# Schematic.net
KiCad netlist of a schematic drawn in Altium Designer
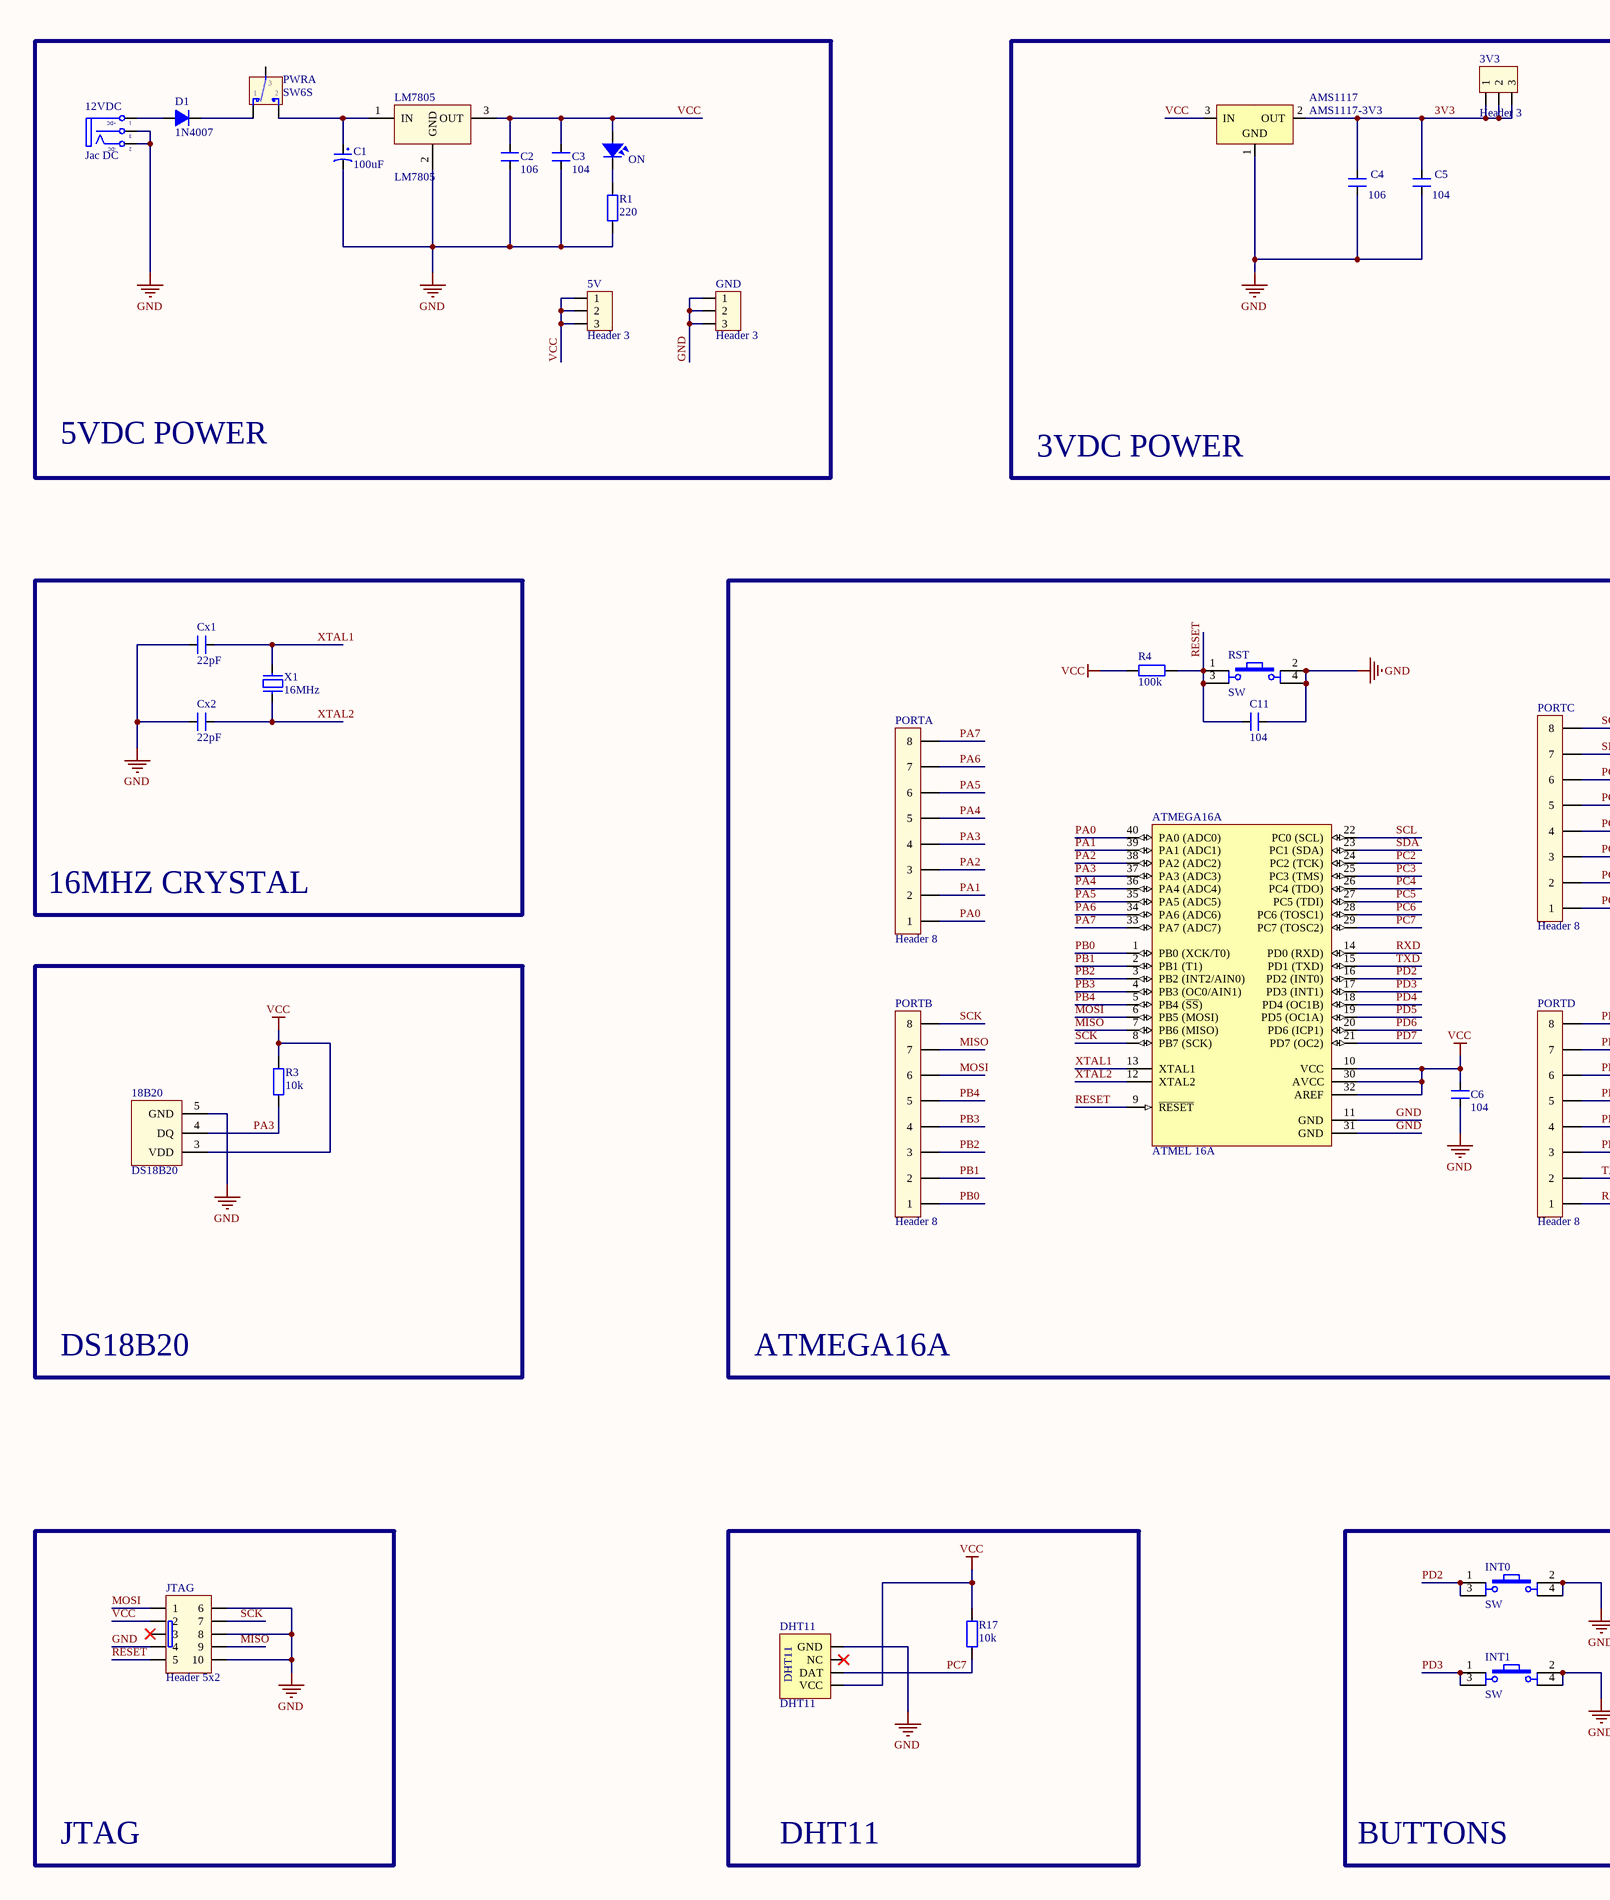
[diagram p0: Schematic.SchDoc, left]
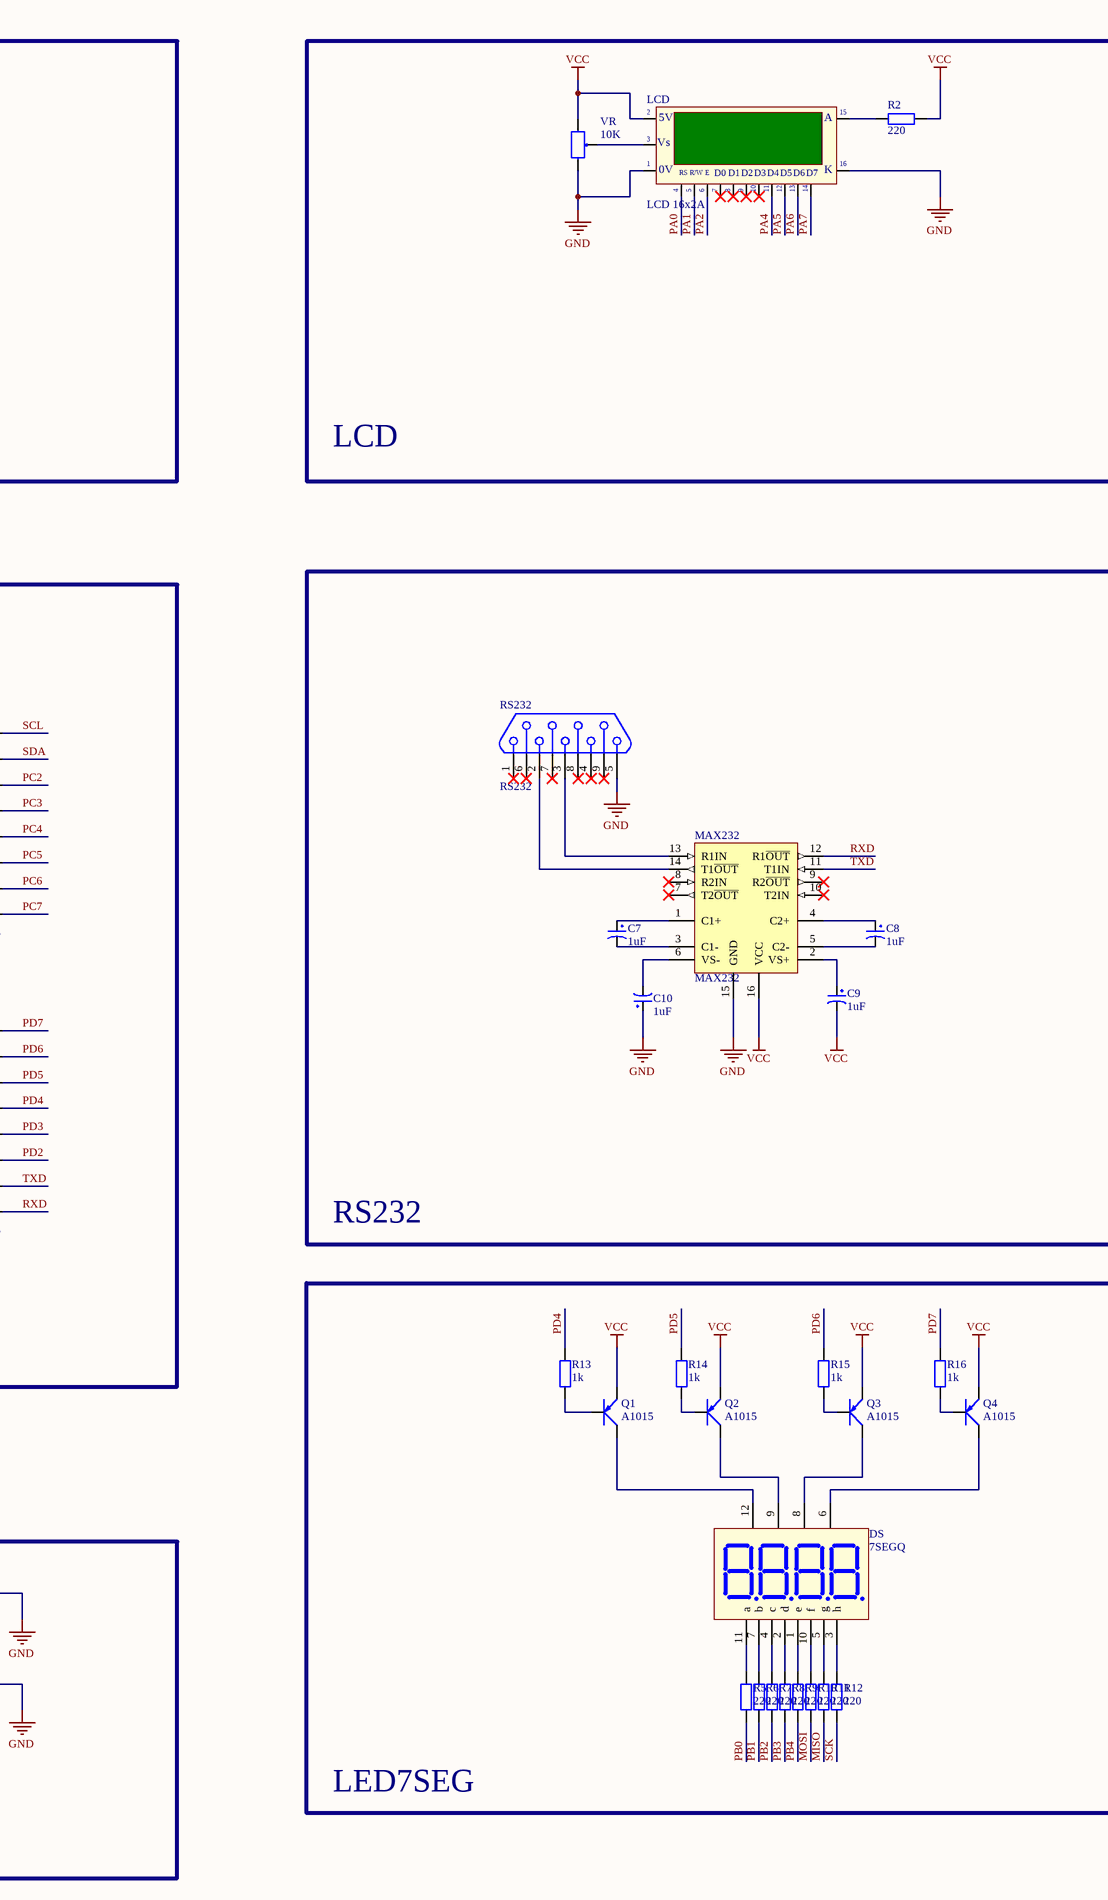
[diagram p1: Schematic.SchDoc, right]

(export (version "E")
  (design (tool "Eeschema 10.0.6"))
  (components
    (comp (ref "3V3")
      (value "Header 3")
      (footprint "HDR1X3")
      (description "Header 3 (Green)")
      (libsource (lib "syhaunguyen") (part "Hed3"))
    )
    (comp (ref "5V")
      (value "Header 3")
      (footprint "HDR1X3")
      (description "Header 3 (Green)")
      (libsource (lib "echipkool-com-library") (part "Hed3"))
    )
    (comp (ref "12VDC")
      (value "Jac DC")
      (footprint "DC-IN")
      (description "Jac DC input")
      (libsource (lib "My Library") (part "DCIN"))
    )
    (comp (ref "18B20")
      (value "DS18B20")
      (footprint "DS18S20")
      (description "High Precision  1-Wire® Digital Thermometer")
      (libsource (lib "syhaunguyen") (part "DS18S20"))
    )
    (comp (ref "AMS1117")
      (value "AMS1117-3V3")
      (footprint "AMS1117-3.3V")
      (description "Linear Voltage Regulator 3.3V 1A 15V Max SOT-223")
      (libsource (lib "lpson") (part "AMS1117-3V3"))
    )
    (comp (ref "ATMEGA16A")
      (value "ATMEL 16A")
      (footprint "DIP40/W0.6")
      (description "8-Bit AVR Microcontroller with 16K Bytes of In-System Programmable Flash Memory")
      (libsource (lib "My Library") (part "ATmega16A-PU"))
    )
    (comp (ref "C1")
      (value "100uF")
      (footprint "CP1/2")
      (description "Cap P  0,1uF < 22uF , 16 - 50V")
      (libsource (lib "echipkool-com-library") (part "CP1"))
    )
    (comp (ref "C2")
      (value "106")
      (footprint "CN2")
      (description "Cap np 104 => 105pF")
      (libsource (lib "echipkool-com-library") (part "CN2"))
    )
    (comp (ref "C3")
      (value "104")
      (footprint "CN2")
      (description "Cap np 104 => 105pF")
      (libsource (lib "echipkool-com-library") (part "CN2"))
    )
    (comp (ref "C4")
      (value "106")
      (footprint "CN2")
      (description "Cap np 104 => 105pF")
      (libsource (lib "syhaunguyen") (part "CN2"))
    )
    (comp (ref "C5")
      (value "104")
      (footprint "CN2")
      (description "Cap np 104 => 105pF")
      (libsource (lib "syhaunguyen") (part "CN2"))
    )
    (comp (ref "C6")
      (value "104")
      (footprint "CN2")
      (fields (field (name "DESIGNED BY") "VanDungEvn"))
      (libsource (lib "syhaunguyen") (part "CN"))
    )
    (comp (ref "C7")
      (value "1uF")
      (footprint "CP1/2")
      (description "Cap P  0,1uF < 22uF , 16 - 50V")
      (libsource (lib "My Library") (part "CP1"))
    )
    (comp (ref "C8")
      (value "1uF")
      (footprint "CP1/2")
      (description "Cap P  0,1uF < 22uF , 16 - 50V")
      (libsource (lib "My Library") (part "CP1"))
    )
    (comp (ref "C9")
      (value "1uF")
      (footprint "CP1/2")
      (description "Cap P  0,1uF < 22uF , 16 - 50V")
      (libsource (lib "My Library") (part "CP1"))
    )
    (comp (ref "C10")
      (value "1uF")
      (footprint "CP1/2")
      (description "Cap P  0,1uF < 22uF , 16 - 50V")
      (libsource (lib "My Library") (part "CP1"))
    )
    (comp (ref "C11")
      (value "104")
      (footprint "CN2")
      (description "Cap np 104 => 105pF")
      (libsource (lib "syhaunguyen") (part "CN2"))
    )
    (comp (ref "Cx1")
      (value "22pF")
      (footprint "CN1")
      (description "Cremic For Xtal 1pF => 100pF")
      (libsource (lib "syhaunguyen") (part "CN0"))
    )
    (comp (ref "Cx2")
      (value "22pF")
      (footprint "CN1")
      (description "Cremic For Xtal 1pF => 100pF")
      (libsource (lib "syhaunguyen") (part "CN0"))
    )
    (comp (ref "D1")
      (value "1N4007")
      (footprint "D1A")
      (description "Diode 1A")
      (libsource (lib "echipkool-com-library") (part "D1A"))
    )
    (comp (ref "DHT11")
      (value "DHT11")
      (footprint "JP4-C1T")
      (fields
        (field (name "MANUFACTURER") "Würth Elektronik eiSos GmbH")
        (field (name "PARTNO") "613004143121")
        (field (name "CREATED BY") "Karrer Zheng")
      )
      (libsource (lib "My Library") (part "DHT11"))
    )
    (comp (ref "DS")
      (value "7SEGQ")
      (footprint "LED7SEG-4-0.56")
      (description "Four 7 Seg Dipslay")
      (libsource (lib "My Library") (part "LED7SEG-4"))
    )
    (comp (ref "GND")
      (value "Header 3")
      (footprint "HDR1X3")
      (description "Header 3 (Green)")
      (libsource (lib "echipkool-com-library") (part "Hed3"))
    )
    (comp (ref "INT0")
      (value "SW")
      (footprint "SW4")
      (description "Switch button 4 pin")
      (libsource (lib "syhaunguyen") (part "SW4"))
    )
    (comp (ref "INT1")
      (value "SW")
      (footprint "SW4")
      (description "Switch button 4 pin")
      (libsource (lib "syhaunguyen") (part "SW4"))
    )
    (comp (ref "JTAG")
      (value "Header 5x2")
      (footprint "Hed2X5")
      (libsource (lib "syhaunguyen") (part "HED5x2"))
    )
    (comp (ref "LCD")
      (value "LCD 16x2A")
      (footprint "LPON_DISPLAY:LCD16x2")
      (description "LCD dipslay 16 char, 2 line")
      (libsource (lib "lpson") (part "LCD16x2A"))
    )
    (comp (ref "LM7805")
      (value "LM7805")
      (footprint "QTO-220")
      (description "On ap +, from + 5 to + 24VDC")
      (libsource (lib "My Library") (part "LM78xx"))
    )
    (comp (ref "MAX232")
      (value "MAX232")
      (footprint "DIP16/W0.3")
      (description "Dual EIA-232 Driver/Receiver")
      (libsource (lib "echipkool-com-library") (part "MAX232"))
    )
    (comp (ref "ON")
      (value "LED")
      (footprint "LED-3")
      (description "LED Single colour Green and Red")
      (libsource (lib "echipkool-com-library") (part "LED"))
    )
    (comp (ref "PORTA")
      (value "Header 8")
      (footprint "HDR1X8")
      (description "Header 8 Vit Broad")
      (libsource (lib "syhaunguyen") (part "HED8V"))
    )
    (comp (ref "PORTB")
      (value "Header 8")
      (footprint "HDR1X8")
      (description "Header 8 Vit Broad")
      (libsource (lib "syhaunguyen") (part "HED8V"))
    )
    (comp (ref "PORTC")
      (value "Header 8")
      (footprint "HDR1X8")
      (description "Header 8 Vit Broad")
      (libsource (lib "syhaunguyen") (part "HED8V"))
    )
    (comp (ref "PORTD")
      (value "Header 8")
      (footprint "HDR1X8")
      (description "Header 8 Vit Broad")
      (libsource (lib "syhaunguyen") (part "HED8V"))
    )
    (comp (ref "PWR")
      (value "SW6S")
      (footprint "SW6")
      (description "SW-DTDP - 6 Pin")
      (libsource (lib "echipkool-com-library") (part "SW6S"))
    )
    (comp (ref "Q1")
      (value "A1015")
      (footprint "QTO-92")
      (description "PNP 600mW, ECB")
      (libsource (lib "syhaunguyen") (part "A1015"))
    )
    (comp (ref "Q2")
      (value "A1015")
      (footprint "QTO-92")
      (description "PNP 600mW, ECB")
      (libsource (lib "syhaunguyen") (part "A1015"))
    )
    (comp (ref "Q3")
      (value "A1015")
      (footprint "QTO-92")
      (description "PNP 600mW, ECB")
      (libsource (lib "syhaunguyen") (part "A1015"))
    )
    (comp (ref "Q4")
      (value "A1015")
      (footprint "QTO-92")
      (description "PNP 600mW, ECB")
      (libsource (lib "syhaunguyen") (part "A1015"))
    )
    (comp (ref "R1")
      (value "220")
      (footprint "R1/4W")
      (description "Resistor 1/4W")
      (libsource (lib "echipkool-com-library") (part "R1/4W"))
    )
    (comp (ref "R2")
      (value "220")
      (footprint "R1/4W")
      (description "Resistor 1/4W")
      (libsource (lib "lpson") (part "R1/4W"))
    )
    (comp (ref "R3")
      (value "10k")
      (footprint "R1/4W")
      (description "Resistor 1/4W")
      (libsource (lib "syhaunguyen") (part "R1/4W"))
    )
    (comp (ref "R4")
      (value "100k")
      (footprint "R1/4W")
      (description "Resistor 1/4W")
      (libsource (lib "syhaunguyen") (part "R1/4W"))
    )
    (comp (ref "R5")
      (value "220")
      (footprint "R1/4W")
      (description "Resistor 1/4W")
      (libsource (lib "syhaunguyen") (part "R1/4W"))
    )
    (comp (ref "R6")
      (value "220")
      (footprint "R1/4W")
      (description "Resistor 1/4W")
      (libsource (lib "syhaunguyen") (part "R1/4W"))
    )
    (comp (ref "R7")
      (value "220")
      (footprint "R1/4W")
      (description "Resistor 1/4W")
      (libsource (lib "syhaunguyen") (part "R1/4W"))
    )
    (comp (ref "R8")
      (value "220")
      (footprint "R1/4W")
      (description "Resistor 1/4W")
      (libsource (lib "syhaunguyen") (part "R1/4W"))
    )
    (comp (ref "R9")
      (value "220")
      (footprint "R1/4W")
      (description "Resistor 1/4W")
      (libsource (lib "syhaunguyen") (part "R1/4W"))
    )
    (comp (ref "R10")
      (value "220")
      (footprint "R1/4W")
      (description "Resistor 1/4W")
      (libsource (lib "syhaunguyen") (part "R1/4W"))
    )
    (comp (ref "R11")
      (value "220")
      (footprint "R1/4W")
      (description "Resistor 1/4W")
      (libsource (lib "syhaunguyen") (part "R1/4W"))
    )
    (comp (ref "R12")
      (value "220")
      (footprint "R1/4W")
      (description "Resistor 1/4W")
      (libsource (lib "syhaunguyen") (part "R1/4W"))
    )
    (comp (ref "R13")
      (value "1k")
      (footprint "R1/4W")
      (description "Resistor 1/4W")
      (libsource (lib "syhaunguyen") (part "R1/4W"))
    )
    (comp (ref "R14")
      (value "1k")
      (footprint "R1/4W")
      (description "Resistor 1/4W")
      (libsource (lib "syhaunguyen") (part "R1/4W"))
    )
    (comp (ref "R15")
      (value "1k")
      (footprint "R1/4W")
      (description "Resistor 1/4W")
      (libsource (lib "syhaunguyen") (part "R1/4W"))
    )
    (comp (ref "R16")
      (value "1k")
      (footprint "R1/4W")
      (description "Resistor 1/4W")
      (libsource (lib "syhaunguyen") (part "R1/4W"))
    )
    (comp (ref "R17")
      (value "10k")
      (footprint "R1/4W")
      (description "Resistor 1/4W")
      (libsource (lib "syhaunguyen") (part "R1/4W"))
    )
    (comp (ref "RS232") (value "RS232") (footprint "DSB 9-M") (libsource (lib "syhaunguyen") (part "COM")))
    (comp (ref "RST")
      (value "SW")
      (footprint "SW4")
      (description "Switch button 4 pin")
      (libsource (lib "syhaunguyen") (part "SW4"))
    )
    (comp (ref "VR")
      (value "10K")
      (footprint "VR1")
      (description "Var Resistor")
      (libsource (lib "syhaunguyen") (part "VR"))
    )
    (comp (ref "X1")
      (value "16MHz")
      (footprint "XT2")
      (description "Crystal For all Crystal 2pin.")
      (libsource (lib "syhaunguyen") (part "XT2"))
    )
  )
  (nets
    (net (code "1") (name "/3V3") (class "Default")
      (node (ref "3V3") (pin "1") (pinfunction "1_1") (pintype "passive"))
      (node (ref "3V3") (pin "2") (pinfunction "2_2") (pintype "passive"))
      (node (ref "3V3") (pin "3") (pinfunction "3_3") (pintype "passive"))
      (node (ref "AMS1117") (pin "2") (pinfunction "OUT_2") (pintype "power_in"))
      (node (ref "C4") (pin "2") (pinfunction "2_2") (pintype "passive"))
      (node (ref "C5") (pin "2") (pinfunction "2_2") (pintype "passive"))
    )
    (net (code "2") (name "/MISO") (class "Default")
      (node (ref "ATMEGA16A") (pin "7") (pinfunction "PB6_(MISO)_7") (pintype "bidirectional"))
      (node (ref "JTAG") (pin "9") (pinfunction "9_9") (pintype "passive"))
      (node (ref "PORTB") (pin "7") (pinfunction "7_7") (pintype "passive"))
      (node (ref "R11") (pin "1") (pinfunction "1_1") (pintype "passive"))
    )
    (net (code "3") (name "/MOSI") (class "Default")
      (node (ref "ATMEGA16A") (pin "6") (pinfunction "PB5_(MOSI)_6") (pintype "bidirectional"))
      (node (ref "JTAG") (pin "1") (pinfunction "1_1") (pintype "passive"))
      (node (ref "PORTB") (pin "6") (pinfunction "6_6") (pintype "passive"))
      (node (ref "R10") (pin "1") (pinfunction "1_1") (pintype "passive"))
    )
    (net (code "4") (name "/PA0") (class "Default")
      (node (ref "ATMEGA16A") (pin "40") (pinfunction "PA0_(ADC0)_40") (pintype "bidirectional"))
      (node (ref "LCD") (pin "4") (pinfunction "RS_4") (pintype "passive"))
      (node (ref "PORTA") (pin "1") (pinfunction "1_1") (pintype "passive"))
    )
    (net (code "5") (name "/PA1") (class "Default")
      (node (ref "ATMEGA16A") (pin "39") (pinfunction "PA1_(ADC1)_39") (pintype "bidirectional"))
      (node (ref "LCD") (pin "5") (pinfunction "R/~{W}_5") (pintype "passive"))
      (node (ref "PORTA") (pin "2") (pinfunction "2_2") (pintype "passive"))
    )
    (net (code "6") (name "/PA2") (class "Default")
      (node (ref "ATMEGA16A") (pin "38") (pinfunction "PA2_(ADC2)_38") (pintype "bidirectional"))
      (node (ref "LCD") (pin "6") (pinfunction "~{EN}_6") (pintype "passive"))
      (node (ref "PORTA") (pin "3") (pinfunction "3_3") (pintype "passive"))
    )
    (net (code "7") (name "/PA3") (class "Default")
      (node (ref "18B20") (pin "4") (pinfunction "DQ_4") (pintype "passive"))
      (node (ref "ATMEGA16A") (pin "37") (pinfunction "PA3_(ADC3)_37") (pintype "bidirectional"))
      (node (ref "PORTA") (pin "4") (pinfunction "4_4") (pintype "passive"))
      (node (ref "R3") (pin "1") (pinfunction "1_1") (pintype "passive"))
    )
    (net (code "8") (name "/PA4") (class "Default")
      (node (ref "ATMEGA16A") (pin "36") (pinfunction "PA4_(ADC4)_36") (pintype "bidirectional"))
      (node (ref "LCD") (pin "11") (pinfunction "D4_11") (pintype "passive"))
      (node (ref "PORTA") (pin "5") (pinfunction "5_5") (pintype "passive"))
    )
    (net (code "9") (name "/PA5") (class "Default")
      (node (ref "ATMEGA16A") (pin "35") (pinfunction "PA5_(ADC5)_35") (pintype "bidirectional"))
      (node (ref "LCD") (pin "12") (pinfunction "D5_12") (pintype "passive"))
      (node (ref "PORTA") (pin "6") (pinfunction "6_6") (pintype "passive"))
    )
    (net (code "10") (name "/PA6") (class "Default")
      (node (ref "ATMEGA16A") (pin "34") (pinfunction "PA6_(ADC6)_34") (pintype "bidirectional"))
      (node (ref "LCD") (pin "13") (pinfunction "D6_13") (pintype "passive"))
      (node (ref "PORTA") (pin "7") (pinfunction "7_7") (pintype "passive"))
    )
    (net (code "11") (name "/PA7") (class "Default")
      (node (ref "ATMEGA16A") (pin "33") (pinfunction "PA7_(ADC7)_33") (pintype "bidirectional"))
      (node (ref "LCD") (pin "14") (pinfunction "D7_14") (pintype "passive"))
      (node (ref "PORTA") (pin "8") (pinfunction "8_8") (pintype "passive"))
    )
    (net (code "12") (name "/PB0") (class "Default")
      (node (ref "ATMEGA16A") (pin "1") (pinfunction "PB0_(XCK/T0)_1") (pintype "bidirectional"))
      (node (ref "PORTB") (pin "1") (pinfunction "1_1") (pintype "passive"))
      (node (ref "R5") (pin "1") (pinfunction "1_1") (pintype "passive"))
    )
    (net (code "13") (name "/PB1") (class "Default")
      (node (ref "ATMEGA16A") (pin "2") (pinfunction "PB1_(T1)_2") (pintype "bidirectional"))
      (node (ref "PORTB") (pin "2") (pinfunction "2_2") (pintype "passive"))
      (node (ref "R6") (pin "1") (pinfunction "1_1") (pintype "passive"))
    )
    (net (code "14") (name "/PB2") (class "Default")
      (node (ref "ATMEGA16A") (pin "3") (pinfunction "PB2_(INT2/AIN0)_3") (pintype "bidirectional"))
      (node (ref "PORTB") (pin "3") (pinfunction "3_3") (pintype "passive"))
      (node (ref "R7") (pin "1") (pinfunction "1_1") (pintype "passive"))
    )
    (net (code "15") (name "/PB3") (class "Default")
      (node (ref "ATMEGA16A") (pin "4") (pinfunction "PB3_(OC0/AIN1)_4") (pintype "bidirectional"))
      (node (ref "PORTB") (pin "4") (pinfunction "4_4") (pintype "passive"))
      (node (ref "R8") (pin "1") (pinfunction "1_1") (pintype "passive"))
    )
    (net (code "16") (name "/PB4") (class "Default")
      (node (ref "ATMEGA16A") (pin "5") (pinfunction "PB4_(~{SS})_5") (pintype "bidirectional"))
      (node (ref "PORTB") (pin "5") (pinfunction "5_5") (pintype "passive"))
      (node (ref "R9") (pin "1") (pinfunction "1_1") (pintype "passive"))
    )
    (net (code "17") (name "/PC2") (class "Default")
      (node (ref "ATMEGA16A") (pin "24") (pinfunction "PC2_(TCK)_24") (pintype "bidirectional"))
      (node (ref "PORTC") (pin "6") (pinfunction "6_6") (pintype "passive"))
    )
    (net (code "18") (name "/PC3") (class "Default")
      (node (ref "ATMEGA16A") (pin "25") (pinfunction "PC3_(TMS)_25") (pintype "bidirectional"))
      (node (ref "PORTC") (pin "5") (pinfunction "5_5") (pintype "passive"))
    )
    (net (code "19") (name "/PC4") (class "Default")
      (node (ref "ATMEGA16A") (pin "26") (pinfunction "PC4_(TDO)_26") (pintype "bidirectional"))
      (node (ref "PORTC") (pin "4") (pinfunction "4_4") (pintype "passive"))
    )
    (net (code "20") (name "/PC5") (class "Default")
      (node (ref "ATMEGA16A") (pin "27") (pinfunction "PC5_(TDI)_27") (pintype "bidirectional"))
      (node (ref "PORTC") (pin "3") (pinfunction "3_3") (pintype "passive"))
    )
    (net (code "21") (name "/PC6") (class "Default")
      (node (ref "ATMEGA16A") (pin "28") (pinfunction "PC6_(TOSC1)_28") (pintype "bidirectional"))
      (node (ref "PORTC") (pin "2") (pinfunction "2_2") (pintype "passive"))
    )
    (net (code "22") (name "/PC7") (class "Default")
      (node (ref "ATMEGA16A") (pin "29") (pinfunction "PC7_(TOSC2)_29") (pintype "bidirectional"))
      (node (ref "DHT11") (pin "2") (pinfunction "DAT_2") (pintype "passive"))
      (node (ref "PORTC") (pin "1") (pinfunction "1_1") (pintype "passive"))
      (node (ref "R17") (pin "1") (pinfunction "1_1") (pintype "passive"))
    )
    (net (code "23") (name "/PD2") (class "Default")
      (node (ref "ATMEGA16A") (pin "16") (pinfunction "PD2_(INT0)_16") (pintype "bidirectional"))
      (node (ref "INT0") (pin "1") (pintype "passive"))
      (node (ref "INT0") (pin "3") (pintype "passive"))
      (node (ref "PORTD") (pin "3") (pinfunction "3_3") (pintype "passive"))
    )
    (net (code "24") (name "/PD3") (class "Default")
      (node (ref "ATMEGA16A") (pin "17") (pinfunction "PD3_(INT1)_17") (pintype "bidirectional"))
      (node (ref "INT1") (pin "1") (pintype "passive"))
      (node (ref "INT1") (pin "3") (pintype "passive"))
      (node (ref "PORTD") (pin "4") (pinfunction "4_4") (pintype "passive"))
    )
    (net (code "25") (name "/PD4") (class "Default")
      (node (ref "ATMEGA16A") (pin "18") (pinfunction "PD4_(OC1B)_18") (pintype "bidirectional"))
      (node (ref "PORTD") (pin "5") (pinfunction "5_5") (pintype "passive"))
      (node (ref "R13") (pin "2") (pinfunction "2_2") (pintype "passive"))
    )
    (net (code "26") (name "/PD5") (class "Default")
      (node (ref "ATMEGA16A") (pin "19") (pinfunction "PD5_(OC1A)_19") (pintype "bidirectional"))
      (node (ref "PORTD") (pin "6") (pinfunction "6_6") (pintype "passive"))
      (node (ref "R14") (pin "2") (pinfunction "2_2") (pintype "passive"))
    )
    (net (code "27") (name "/PD6") (class "Default")
      (node (ref "ATMEGA16A") (pin "20") (pinfunction "PD6_(ICP1)_20") (pintype "bidirectional"))
      (node (ref "PORTD") (pin "7") (pinfunction "7_7") (pintype "passive"))
      (node (ref "R15") (pin "2") (pinfunction "2_2") (pintype "passive"))
    )
    (net (code "28") (name "/PD7") (class "Default")
      (node (ref "ATMEGA16A") (pin "21") (pinfunction "PD7_(OC2)_21") (pintype "bidirectional"))
      (node (ref "PORTD") (pin "8") (pinfunction "8_8") (pintype "passive"))
      (node (ref "R16") (pin "2") (pinfunction "2_2") (pintype "passive"))
    )
    (net (code "29") (name "/RESET") (class "Default")
      (node (ref "ATMEGA16A") (pin "9") (pinfunction "~{RESET}_9") (pintype "input"))
      (node (ref "C11") (pin "1") (pinfunction "1_1") (pintype "passive"))
      (node (ref "JTAG") (pin "5") (pinfunction "5_5") (pintype "passive"))
      (node (ref "R4") (pin "2") (pinfunction "2_2") (pintype "passive"))
      (node (ref "RST") (pin "1") (pintype "passive"))
      (node (ref "RST") (pin "3") (pintype "passive"))
    )
    (net (code "30") (name "/RXD") (class "Default")
      (node (ref "ATMEGA16A") (pin "14") (pinfunction "PD0_(RXD)_14") (pintype "bidirectional"))
      (node (ref "MAX232") (pin "12") (pinfunction "R1~{OUT}_12") (pintype "output"))
      (node (ref "PORTD") (pin "1") (pinfunction "1_1") (pintype "passive"))
    )
    (net (code "31") (name "/SCK") (class "Default")
      (node (ref "ATMEGA16A") (pin "8") (pinfunction "PB7_(SCK)_8") (pintype "bidirectional"))
      (node (ref "JTAG") (pin "7") (pinfunction "7_7") (pintype "passive"))
      (node (ref "PORTB") (pin "8") (pinfunction "8_8") (pintype "passive"))
      (node (ref "R12") (pin "1") (pinfunction "1_1") (pintype "passive"))
    )
    (net (code "32") (name "/SCL") (class "Default")
      (node (ref "ATMEGA16A") (pin "22") (pinfunction "PC0_(SCL)_22") (pintype "bidirectional"))
      (node (ref "PORTC") (pin "8") (pinfunction "8_8") (pintype "passive"))
    )
    (net (code "33") (name "/SDA") (class "Default")
      (node (ref "ATMEGA16A") (pin "23") (pinfunction "PC1_(SDA)_23") (pintype "bidirectional"))
      (node (ref "PORTC") (pin "7") (pinfunction "7_7") (pintype "passive"))
    )
    (net (code "34") (name "/TXD") (class "Default")
      (node (ref "ATMEGA16A") (pin "15") (pinfunction "PD1_(TXD)_15") (pintype "bidirectional"))
      (node (ref "MAX232") (pin "11") (pinfunction "T1IN_11") (pintype "input"))
      (node (ref "PORTD") (pin "2") (pinfunction "2_2") (pintype "passive"))
    )
    (net (code "35") (name "/XTAL1") (class "Default")
      (node (ref "ATMEGA16A") (pin "13") (pinfunction "XTAL1_13") (pintype "passive"))
      (node (ref "Cx1") (pin "2") (pinfunction "2_2") (pintype "passive"))
      (node (ref "X1") (pin "2") (pinfunction "2_2") (pintype "passive"))
    )
    (net (code "36") (name "/XTAL2") (class "Default")
      (node (ref "ATMEGA16A") (pin "12") (pinfunction "XTAL2_12") (pintype "passive"))
      (node (ref "Cx2") (pin "2") (pinfunction "2_2") (pintype "passive"))
      (node (ref "X1") (pin "1") (pinfunction "1_1") (pintype "passive"))
    )
    (net (code "37") (name "GND") (class "Default")
      (node (ref "12VDC") (pin "2") (pinfunction "TN_2") (pintype "passive"))
      (node (ref "12VDC") (pin "3") (pinfunction "S_3") (pintype "power_in"))
      (node (ref "18B20") (pin "5") (pinfunction "GND_5") (pintype "passive"))
      (node (ref "AMS1117") (pin "1") (pinfunction "GND_1") (pintype "power_in"))
      (node (ref "ATMEGA16A") (pin "11") (pinfunction "GND_11") (pintype "power_in"))
      (node (ref "ATMEGA16A") (pin "31") (pinfunction "GND_31") (pintype "power_in"))
      (node (ref "C1") (pin "2") (pinfunction "2_2") (pintype "passive"))
      (node (ref "C10") (pin "1") (pinfunction "1_1") (pintype "passive"))
      (node (ref "C11") (pin "2") (pinfunction "2_2") (pintype "passive"))
      (node (ref "C2") (pin "1") (pinfunction "1_1") (pintype "passive"))
      (node (ref "C3") (pin "1") (pinfunction "1_1") (pintype "passive"))
      (node (ref "C4") (pin "1") (pinfunction "1_1") (pintype "passive"))
      (node (ref "C5") (pin "1") (pinfunction "1_1") (pintype "passive"))
      (node (ref "C6") (pin "1") (pinfunction "1_1") (pintype "passive"))
      (node (ref "Cx1") (pin "1") (pinfunction "1_1") (pintype "passive"))
      (node (ref "Cx2") (pin "1") (pinfunction "1_1") (pintype "passive"))
      (node (ref "DHT11") (pin "4") (pinfunction "GND_4") (pintype "passive"))
      (node (ref "GND") (pin "1") (pinfunction "1_1") (pintype "passive"))
      (node (ref "GND") (pin "2") (pinfunction "2_2") (pintype "passive"))
      (node (ref "GND") (pin "3") (pinfunction "3_3") (pintype "passive"))
      (node (ref "INT0") (pin "2") (pintype "passive"))
      (node (ref "INT0") (pin "4") (pintype "passive"))
      (node (ref "INT1") (pin "2") (pintype "passive"))
      (node (ref "INT1") (pin "4") (pintype "passive"))
      (node (ref "JTAG") (pin "10") (pinfunction "10_10") (pintype "passive"))
      (node (ref "JTAG") (pin "4") (pinfunction "4_4") (pintype "passive"))
      (node (ref "JTAG") (pin "6") (pinfunction "6_6") (pintype "passive"))
      (node (ref "JTAG") (pin "8") (pinfunction "8_8") (pintype "passive"))
      (node (ref "LCD") (pin "1") (pinfunction "GND_1") (pintype "passive"))
      (node (ref "LCD") (pin "16") (pinfunction "K_16") (pintype "passive"))
      (node (ref "LM7805") (pin "2") (pinfunction "GND_2") (pintype "passive"))
      (node (ref "MAX232") (pin "15") (pinfunction "GND_15") (pintype "power_in"))
      (node (ref "R1") (pin "1") (pinfunction "1_1") (pintype "passive"))
      (node (ref "RS232") (pin "5") (pinfunction "5_5") (pintype "passive"))
      (node (ref "RST") (pin "2") (pintype "passive"))
      (node (ref "RST") (pin "4") (pintype "passive"))
      (node (ref "VR") (pin "3") (pinfunction "3_3") (pintype "passive"))
    )
    (net (code "38") (name "Net-(12VDC-T)") (class "Default")
      (node (ref "12VDC") (pin "1") (pinfunction "T_1") (pintype "passive"))
      (node (ref "D1") (pin "1") (pinfunction "A_1") (pintype "passive"))
    )
    (net (code "39") (name "Net-(D1-K)") (class "Default")
      (node (ref "D1") (pin "2") (pinfunction "K_2") (pintype "passive"))
      (node (ref "PWR") (pin "1") (pinfunction "1_1") (pintype "passive"))
    )
    (net (code "40") (name "Net-(DS-V1)") (class "Default")
      (node (ref "DS") (pin "12") (pinfunction "V1_12") (pintype "passive"))
      (node (ref "Q1") (pin "2") (pinfunction "C_2") (pintype "passive"))
    )
    (net (code "41") (name "Net-(DS-V2)") (class "Default")
      (node (ref "DS") (pin "9") (pinfunction "V2_9") (pintype "passive"))
      (node (ref "Q2") (pin "2") (pinfunction "C_2") (pintype "passive"))
    )
    (net (code "42") (name "Net-(DS-V3)") (class "Default")
      (node (ref "DS") (pin "8") (pinfunction "V3_8") (pintype "passive"))
      (node (ref "Q3") (pin "2") (pinfunction "C_2") (pintype "passive"))
    )
    (net (code "43") (name "Net-(DS-V4)") (class "Default")
      (node (ref "DS") (pin "6") (pinfunction "V4_6") (pintype "passive"))
      (node (ref "Q4") (pin "2") (pinfunction "C_2") (pintype "passive"))
    )
    (net (code "44") (name "Net-(DS-a)") (class "Default")
      (node (ref "DS") (pin "11") (pinfunction "a_11") (pintype "passive"))
      (node (ref "R5") (pin "2") (pinfunction "2_2") (pintype "passive"))
    )
    (net (code "45") (name "Net-(DS-b)") (class "Default")
      (node (ref "DS") (pin "7") (pinfunction "b_7") (pintype "passive"))
      (node (ref "R6") (pin "2") (pinfunction "2_2") (pintype "passive"))
    )
    (net (code "46") (name "Net-(DS-c)") (class "Default")
      (node (ref "DS") (pin "4") (pinfunction "c_4") (pintype "passive"))
      (node (ref "R7") (pin "2") (pinfunction "2_2") (pintype "passive"))
    )
    (net (code "47") (name "Net-(DS-d)") (class "Default")
      (node (ref "DS") (pin "2") (pinfunction "d_2") (pintype "passive"))
      (node (ref "R8") (pin "2") (pinfunction "2_2") (pintype "passive"))
    )
    (net (code "48") (name "Net-(DS-e)") (class "Default")
      (node (ref "DS") (pin "1") (pinfunction "e_1") (pintype "passive"))
      (node (ref "R9") (pin "2") (pinfunction "2_2") (pintype "passive"))
    )
    (net (code "49") (name "Net-(DS-f)") (class "Default")
      (node (ref "DS") (pin "10") (pinfunction "f_10") (pintype "passive"))
      (node (ref "R10") (pin "2") (pinfunction "2_2") (pintype "passive"))
    )
    (net (code "50") (name "Net-(DS-g)") (class "Default")
      (node (ref "DS") (pin "5") (pinfunction "g_5") (pintype "passive"))
      (node (ref "R11") (pin "2") (pinfunction "2_2") (pintype "passive"))
    )
    (net (code "51") (name "Net-(DS-h)") (class "Default")
      (node (ref "DS") (pin "3") (pinfunction "h_3") (pintype "passive"))
      (node (ref "R12") (pin "2") (pinfunction "2_2") (pintype "passive"))
    )
    (net (code "52") (name "Net-(LCD-A)") (class "Default")
      (node (ref "LCD") (pin "15") (pinfunction "A_15") (pintype "passive"))
      (node (ref "R2") (pin "1") (pinfunction "1_1") (pintype "passive"))
    )
    (net (code "53") (name "Net-(LCD-VEE)") (class "Default")
      (node (ref "LCD") (pin "3") (pinfunction "VEE_3") (pintype "passive"))
      (node (ref "VR") (pin "2") (pinfunction "2_2") (pintype "passive"))
    )
    (net (code "54") (name "Net-(LM7805-IN)") (class "Default")
      (node (ref "C1") (pin "1") (pinfunction "1_1") (pintype "passive"))
      (node (ref "LM7805") (pin "1") (pinfunction "IN_1") (pintype "passive"))
      (node (ref "PWR") (pin "2") (pinfunction "2_2") (pintype "passive"))
    )
    (net (code "55") (name "Net-(MAX232-C1+)") (class "Default")
      (node (ref "C7") (pin "1") (pinfunction "1_1") (pintype "passive"))
      (node (ref "MAX232") (pin "1") (pinfunction "C1+_1") (pintype "passive"))
    )
    (net (code "56") (name "Net-(MAX232-C1-)") (class "Default")
      (node (ref "C7") (pin "2") (pinfunction "2_2") (pintype "passive"))
      (node (ref "MAX232") (pin "3") (pinfunction "C1-_3") (pintype "passive"))
    )
    (net (code "57") (name "Net-(MAX232-C2+)") (class "Default")
      (node (ref "C8") (pin "1") (pinfunction "1_1") (pintype "passive"))
      (node (ref "MAX232") (pin "4") (pinfunction "C2+_4") (pintype "passive"))
    )
    (net (code "58") (name "Net-(MAX232-C2-)") (class "Default")
      (node (ref "C8") (pin "2") (pinfunction "2_2") (pintype "passive"))
      (node (ref "MAX232") (pin "5") (pinfunction "C2-_5") (pintype "passive"))
    )
    (net (code "59") (name "Net-(MAX232-R1IN)") (class "Default")
      (node (ref "MAX232") (pin "13") (pinfunction "R1IN_13") (pintype "input"))
      (node (ref "RS232") (pin "3") (pinfunction "3_3") (pintype "passive"))
    )
    (net (code "60") (name "Net-(MAX232-T1~{OUT})") (class "Default")
      (node (ref "MAX232") (pin "14") (pinfunction "T1~{OUT}_14") (pintype "output"))
      (node (ref "RS232") (pin "2") (pinfunction "2_2") (pintype "passive"))
    )
    (net (code "61") (name "Net-(MAX232-VS+)") (class "Default")
      (node (ref "C9") (pin "1") (pinfunction "1_1") (pintype "passive"))
      (node (ref "MAX232") (pin "2") (pinfunction "VS+_2") (pintype "power_in"))
    )
    (net (code "62") (name "Net-(MAX232-VS-)") (class "Default")
      (node (ref "C10") (pin "2") (pinfunction "2_2") (pintype "passive"))
      (node (ref "MAX232") (pin "6") (pinfunction "VS-_6") (pintype "power_in"))
    )
    (net (code "63") (name "Net-(ON-Pad2)") (class "Default")
      (node (ref "ON") (pin "2") (pinfunction "2_2") (pintype "passive"))
      (node (ref "R1") (pin "2") (pinfunction "2_2") (pintype "passive"))
    )
    (net (code "64") (name "Net-(Q1-B)") (class "Default")
      (node (ref "Q1") (pin "3") (pinfunction "B_3") (pintype "passive"))
      (node (ref "R13") (pin "1") (pinfunction "1_1") (pintype "passive"))
    )
    (net (code "65") (name "Net-(Q2-B)") (class "Default")
      (node (ref "Q2") (pin "3") (pinfunction "B_3") (pintype "passive"))
      (node (ref "R14") (pin "1") (pinfunction "1_1") (pintype "passive"))
    )
    (net (code "66") (name "Net-(Q3-B)") (class "Default")
      (node (ref "Q3") (pin "3") (pinfunction "B_3") (pintype "passive"))
      (node (ref "R15") (pin "1") (pinfunction "1_1") (pintype "passive"))
    )
    (net (code "67") (name "Net-(Q4-B)") (class "Default")
      (node (ref "Q4") (pin "3") (pinfunction "B_3") (pintype "passive"))
      (node (ref "R16") (pin "1") (pinfunction "1_1") (pintype "passive"))
    )
    (net (code "68") (name "VCC") (class "Default")
      (node (ref "18B20") (pin "3") (pinfunction "VDD_3") (pintype "passive"))
      (node (ref "5V") (pin "1") (pinfunction "1_1") (pintype "passive"))
      (node (ref "5V") (pin "2") (pinfunction "2_2") (pintype "passive"))
      (node (ref "5V") (pin "3") (pinfunction "3_3") (pintype "passive"))
      (node (ref "AMS1117") (pin "3") (pinfunction "IN_3") (pintype "power_in"))
      (node (ref "ATMEGA16A") (pin "10") (pinfunction "VCC_10") (pintype "power_in"))
      (node (ref "ATMEGA16A") (pin "30") (pinfunction "AVCC_30") (pintype "power_in"))
      (node (ref "ATMEGA16A") (pin "32") (pinfunction "AREF_32") (pintype "power_in"))
      (node (ref "C2") (pin "2") (pinfunction "2_2") (pintype "passive"))
      (node (ref "C3") (pin "2") (pinfunction "2_2") (pintype "passive"))
      (node (ref "C6") (pin "2") (pinfunction "2_2") (pintype "passive"))
      (node (ref "C9") (pin "2") (pinfunction "2_2") (pintype "passive"))
      (node (ref "DHT11") (pin "1") (pinfunction "VCC_1") (pintype "passive"))
      (node (ref "JTAG") (pin "2") (pinfunction "2_2") (pintype "passive"))
      (node (ref "LCD") (pin "2") (pinfunction "VDD_2") (pintype "passive"))
      (node (ref "LM7805") (pin "3") (pinfunction "OUT_3") (pintype "passive"))
      (node (ref "MAX232") (pin "16") (pinfunction "VCC_16") (pintype "power_in"))
      (node (ref "ON") (pin "1") (pinfunction "1_1") (pintype "passive"))
      (node (ref "Q1") (pin "1") (pinfunction "E_1") (pintype "passive"))
      (node (ref "Q2") (pin "1") (pinfunction "E_1") (pintype "passive"))
      (node (ref "Q3") (pin "1") (pinfunction "E_1") (pintype "passive"))
      (node (ref "Q4") (pin "1") (pinfunction "E_1") (pintype "passive"))
      (node (ref "R17") (pin "2") (pinfunction "2_2") (pintype "passive"))
      (node (ref "R2") (pin "2") (pinfunction "2_2") (pintype "passive"))
      (node (ref "R3") (pin "2") (pinfunction "2_2") (pintype "passive"))
      (node (ref "R4") (pin "1") (pinfunction "1_1") (pintype "passive"))
      (node (ref "VR") (pin "1") (pinfunction "1_1") (pintype "passive"))
    )
    (net (code "69") (name "unconnected-(AMS1117-OUT-Pad4)") (class "Default")
      (node (ref "AMS1117") (pin "4") (pinfunction "OUT_4") (pintype "power_in"))
    )
    (net (code "70") (name "unconnected-(DHT11-NC-Pad3)") (class "Default")
      (node (ref "DHT11") (pin "3") (pinfunction "NC_3") (pintype "passive+no_connect"))
    )
    (net (code "71") (name "unconnected-(JTAG-Pad3)") (class "Default")
      (node (ref "JTAG") (pin "3") (pinfunction "3_3") (pintype "passive+no_connect"))
    )
    (net (code "72") (name "unconnected-(LCD-D0-Pad7)") (class "Default")
      (node (ref "LCD") (pin "7") (pinfunction "D0_7") (pintype "passive+no_connect"))
    )
    (net (code "73") (name "unconnected-(LCD-D1-Pad8)") (class "Default")
      (node (ref "LCD") (pin "8") (pinfunction "D1_8") (pintype "passive+no_connect"))
    )
    (net (code "74") (name "unconnected-(LCD-D2-Pad9)") (class "Default")
      (node (ref "LCD") (pin "9") (pinfunction "D2_9") (pintype "passive+no_connect"))
    )
    (net (code "75") (name "unconnected-(LCD-D3-Pad10)") (class "Default")
      (node (ref "LCD") (pin "10") (pinfunction "D3_10") (pintype "passive+no_connect"))
    )
    (net (code "76") (name "unconnected-(MAX232-R2IN-Pad8)") (class "Default")
      (node (ref "MAX232") (pin "8") (pinfunction "R2IN_8") (pintype "input+no_connect"))
    )
    (net (code "77") (name "unconnected-(MAX232-R2~{OUT}-Pad9)") (class "Default")
      (node (ref "MAX232") (pin "9") (pinfunction "R2~{OUT}_9") (pintype "output+no_connect"))
    )
    (net (code "78") (name "unconnected-(MAX232-T2IN-Pad10)") (class "Default")
      (node (ref "MAX232") (pin "10") (pinfunction "T2IN_10") (pintype "input+no_connect"))
    )
    (net (code "79") (name "unconnected-(MAX232-T2~{OUT}-Pad7)") (class "Default")
      (node (ref "MAX232") (pin "7") (pinfunction "T2~{OUT}_7") (pintype "output+no_connect"))
    )
    (net (code "80") (name "unconnected-(PWR-Pad3)") (class "Default")
      (node (ref "PWR") (pin "3") (pinfunction "3_3") (pintype "passive"))
    )
    (net (code "81") (name "unconnected-(RS232-Pad1)") (class "Default")
      (node (ref "RS232") (pin "1") (pinfunction "1_1") (pintype "passive+no_connect"))
    )
    (net (code "82") (name "unconnected-(RS232-Pad4)") (class "Default")
      (node (ref "RS232") (pin "4") (pinfunction "4_4") (pintype "passive+no_connect"))
    )
    (net (code "83") (name "unconnected-(RS232-Pad6)") (class "Default")
      (node (ref "RS232") (pin "6") (pinfunction "6_6") (pintype "passive+no_connect"))
    )
    (net (code "84") (name "unconnected-(RS232-Pad7)") (class "Default")
      (node (ref "RS232") (pin "7") (pinfunction "7_7") (pintype "passive+no_connect"))
    )
    (net (code "85") (name "unconnected-(RS232-Pad8)") (class "Default")
      (node (ref "RS232") (pin "8") (pinfunction "8_8") (pintype "passive+no_connect"))
    )
    (net (code "86") (name "unconnected-(RS232-Pad9)") (class "Default")
      (node (ref "RS232") (pin "9") (pinfunction "9_9") (pintype "passive+no_connect"))
    )
  )
)
